# GalvoDAC.net
KiCad netlist of a schematic drawn in Altium Designer
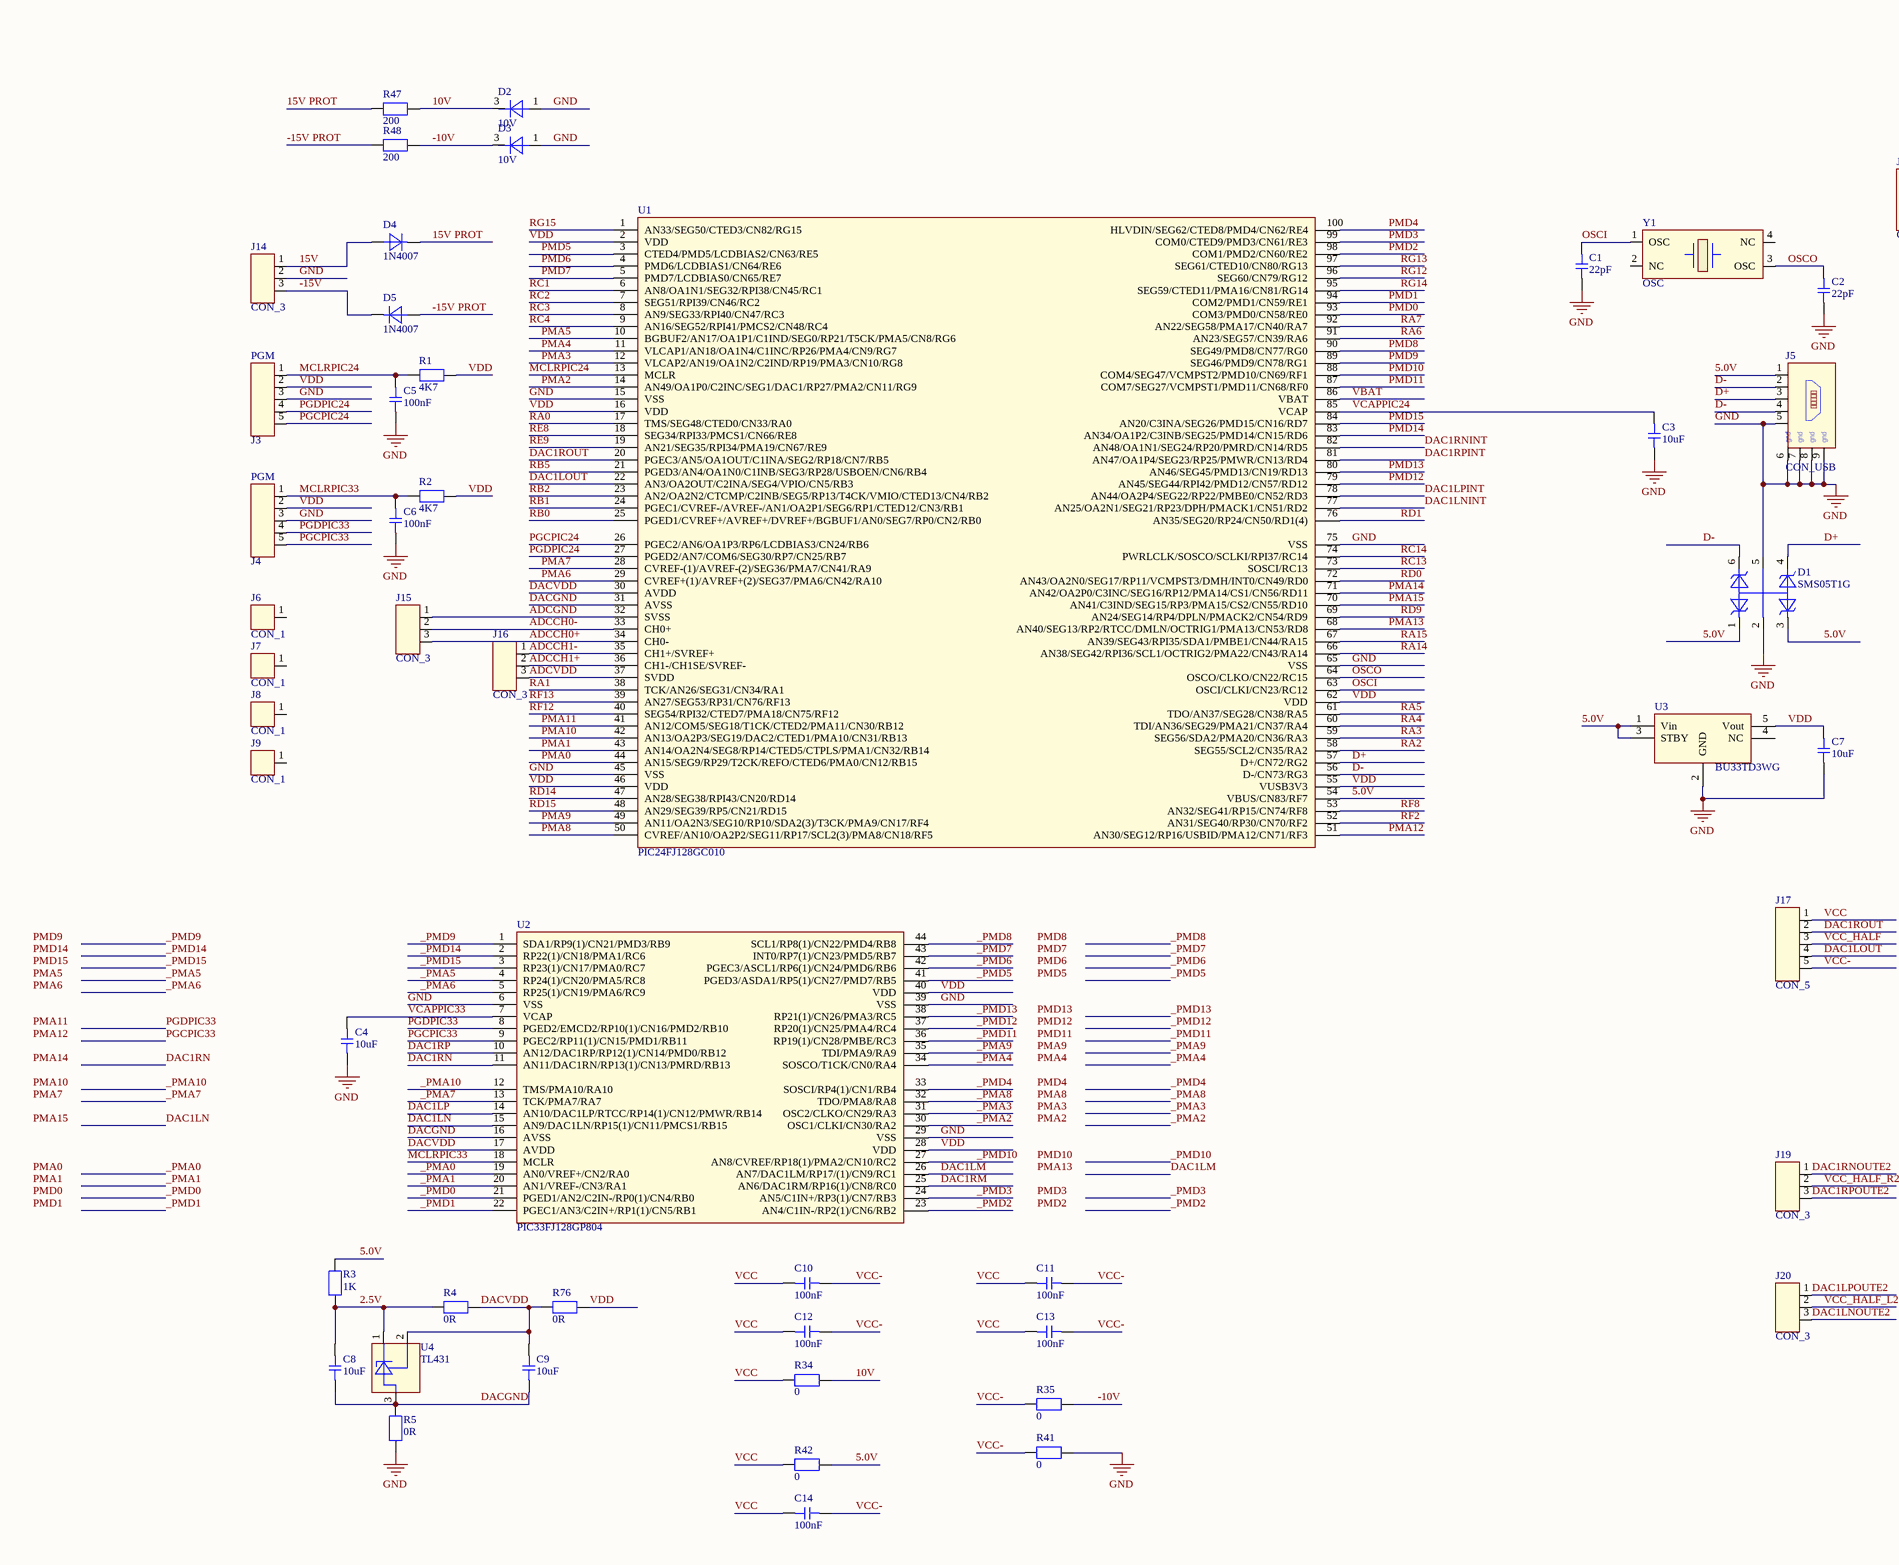
[diagram p0: GalvoDAC.SchDoc, left]
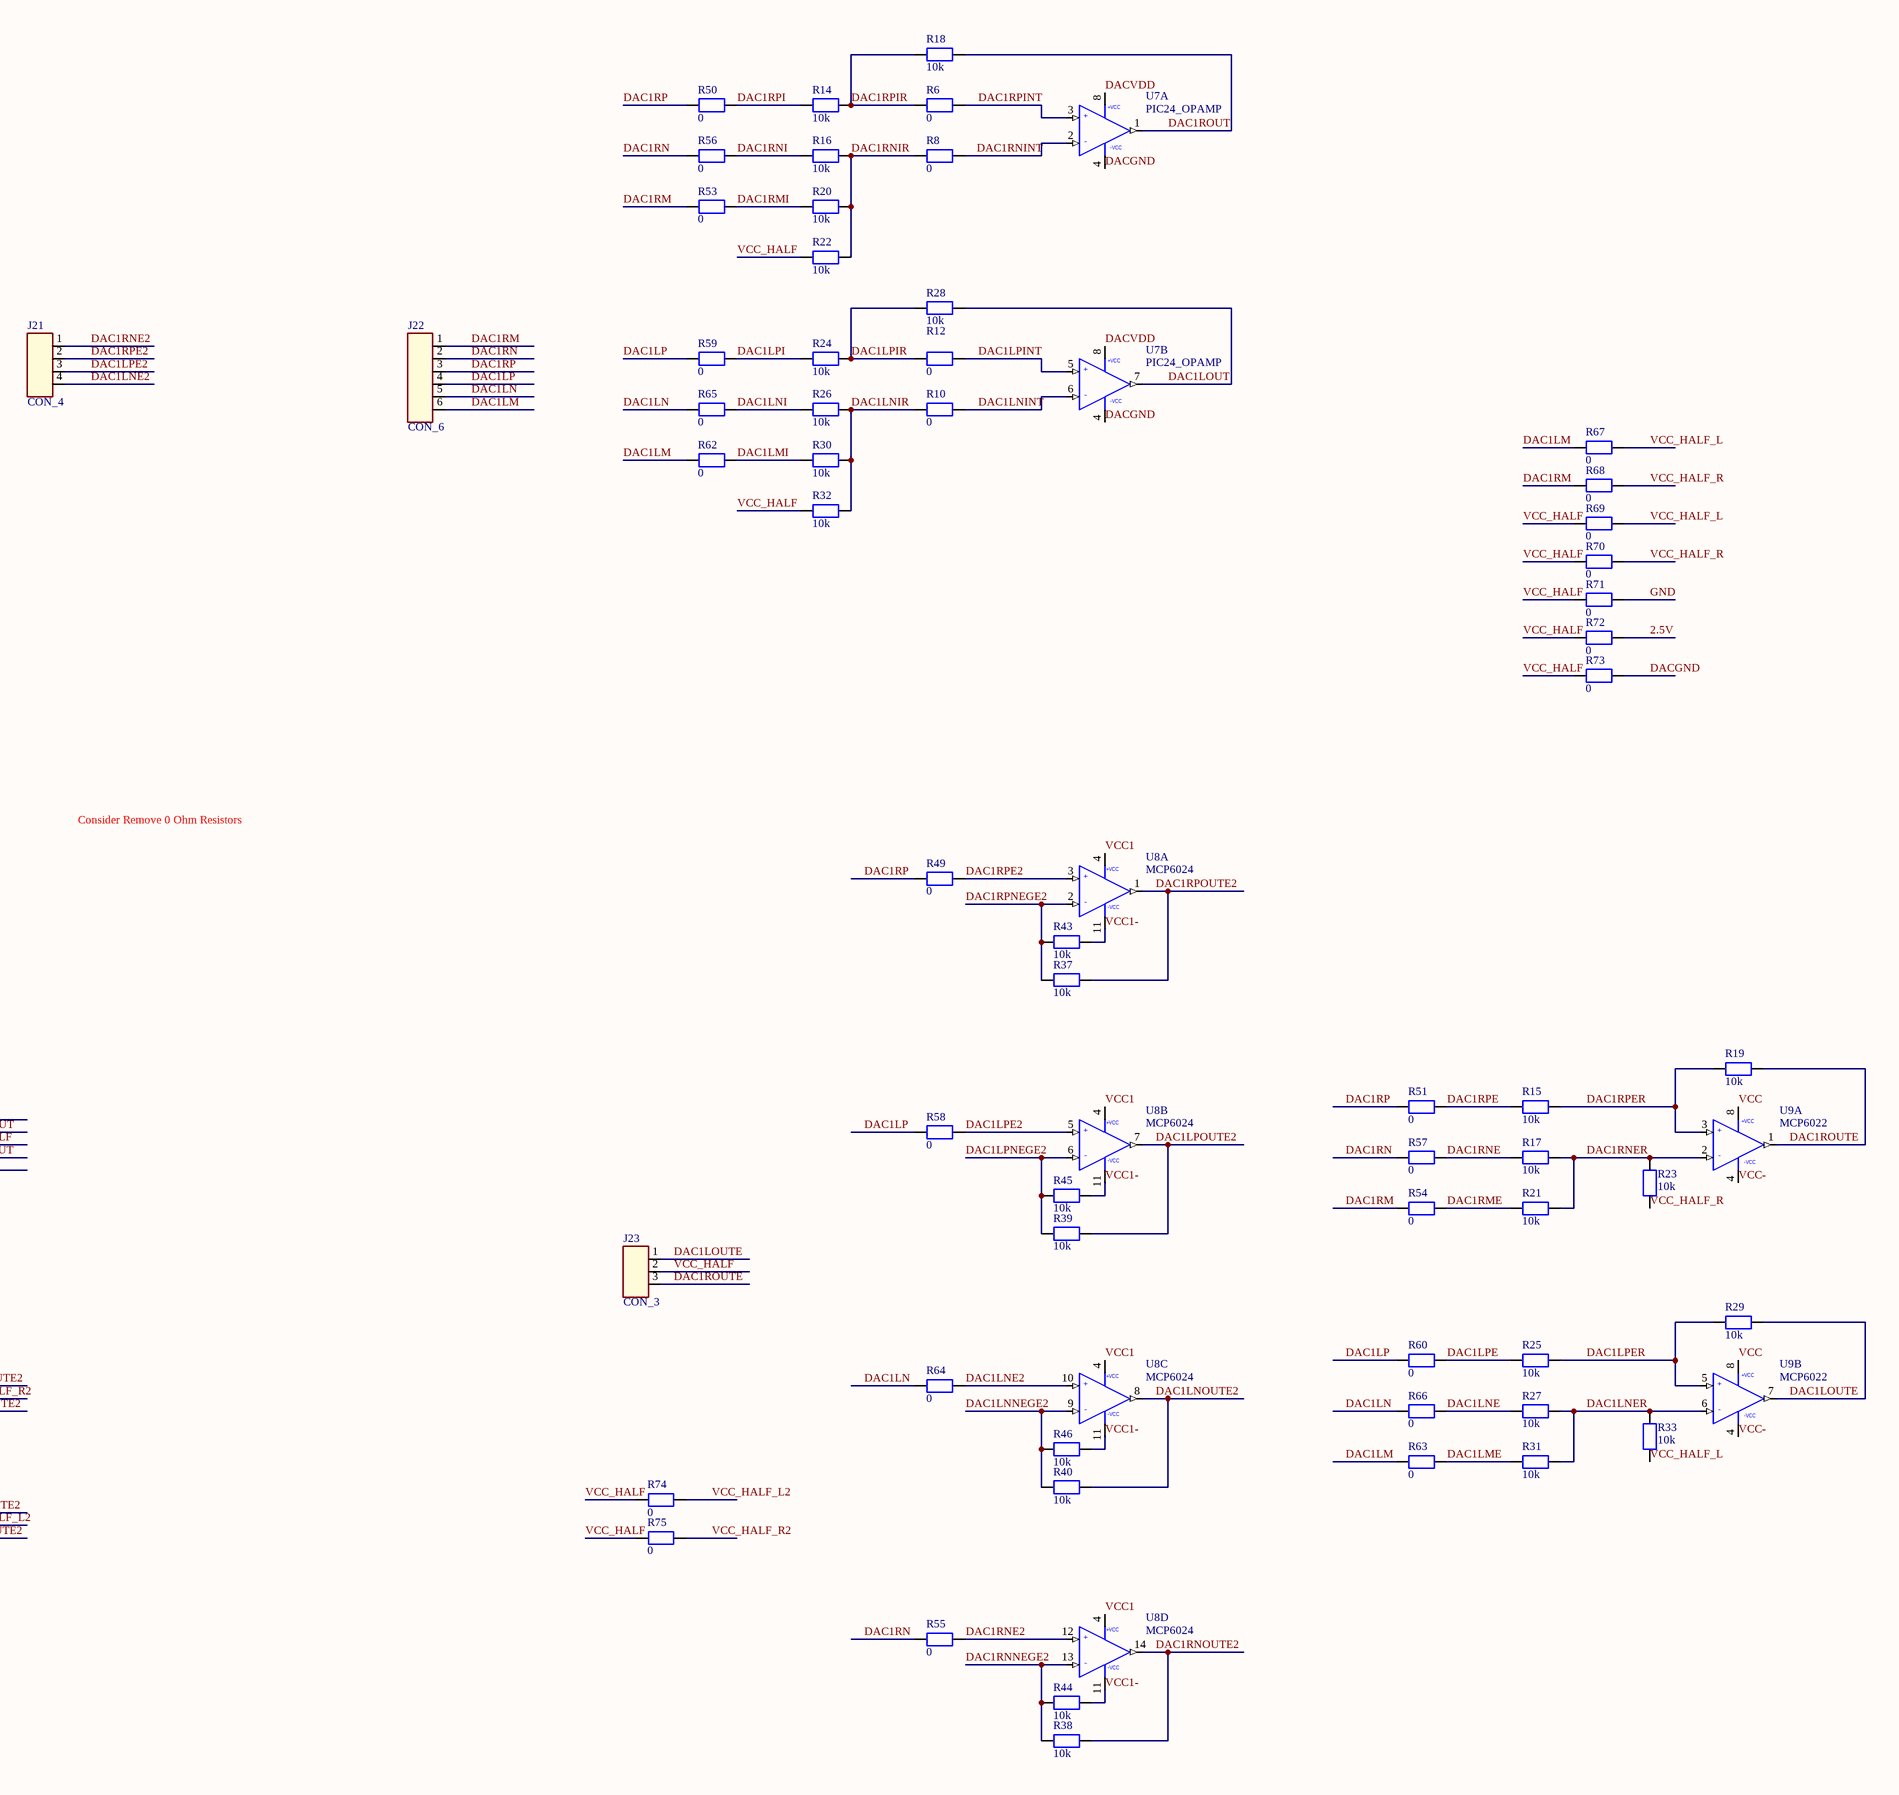
[diagram p1: GalvoDAC.SchDoc, right]

(export (version "E")
  (design (tool "Eeschema 10.0.6"))
  (components
    (comp (ref "C1")
      (value "22pF")
      (footprint "0603_C")
      (description "Capacitor")
      (fields (field (name "Comment") "C") (field (name "PUBLISHER") "Altium Limited"))
      (libsource (lib "HEX") (part "C"))
    )
    (comp (ref "C2")
      (value "22pF")
      (footprint "0603_C")
      (description "Capacitor")
      (fields (field (name "Comment") "C") (field (name "PUBLISHER") "Altium Limited"))
      (libsource (lib "HEX") (part "C"))
    )
    (comp (ref "C3")
      (value "10uF")
      (footprint "0603_C")
      (description "Capacitor")
      (fields (field (name "Comment") "C") (field (name "PUBLISHER") "Altium Limited"))
      (libsource (lib "HEX") (part "C"))
    )
    (comp (ref "C4")
      (value "10uF")
      (footprint "0603_C")
      (description "Capacitor")
      (fields (field (name "Comment") "C") (field (name "PUBLISHER") "Altium Limited"))
      (libsource (lib "HEX") (part "C"))
    )
    (comp (ref "C5")
      (value "100nF")
      (footprint "0603_C")
      (description "Capacitor")
      (fields (field (name "Comment") "C") (field (name "PUBLISHER") "Altium Limited"))
      (libsource (lib "HEX") (part "C"))
    )
    (comp (ref "C6")
      (value "100nF")
      (footprint "0603_C")
      (description "Capacitor")
      (fields (field (name "Comment") "C") (field (name "PUBLISHER") "Altium Limited"))
      (libsource (lib "HEX") (part "C"))
    )
    (comp (ref "C7")
      (value "10uF")
      (footprint "0603_C")
      (description "Capacitor")
      (fields (field (name "Comment") "C") (field (name "PUBLISHER") "Altium Limited"))
      (libsource (lib "HEX") (part "C"))
    )
    (comp (ref "C8")
      (value "10uF")
      (footprint "0603_C")
      (description "Capacitor")
      (fields (field (name "Comment") "C") (field (name "PUBLISHER") "Altium Limited"))
      (libsource (lib "HEX") (part "C"))
    )
    (comp (ref "C9")
      (value "10uF")
      (footprint "0603_C")
      (description "Capacitor")
      (fields (field (name "Comment") "C") (field (name "PUBLISHER") "Altium Limited"))
      (libsource (lib "HEX") (part "C"))
    )
    (comp (ref "C10")
      (value "100nF")
      (footprint "0603_C")
      (description "Capacitor")
      (fields (field (name "Comment") "C") (field (name "PUBLISHER") "Altium Limited"))
      (libsource (lib "HEX") (part "C"))
    )
    (comp (ref "C11")
      (value "100nF")
      (footprint "0603_C")
      (description "Capacitor")
      (fields (field (name "Comment") "C") (field (name "PUBLISHER") "Altium Limited"))
      (libsource (lib "HEX") (part "C"))
    )
    (comp (ref "C12")
      (value "100nF")
      (footprint "0603_C")
      (description "Capacitor")
      (fields (field (name "Comment") "C") (field (name "PUBLISHER") "Altium Limited"))
      (libsource (lib "HEX") (part "C"))
    )
    (comp (ref "C13")
      (value "100nF")
      (footprint "0603_C")
      (description "Capacitor")
      (fields (field (name "Comment") "C") (field (name "PUBLISHER") "Altium Limited"))
      (libsource (lib "HEX") (part "C"))
    )
    (comp (ref "C14")
      (value "100nF")
      (footprint "0603_C")
      (description "Capacitor")
      (fields (field (name "Comment") "C") (field (name "PUBLISHER") "Altium Limited"))
      (libsource (lib "HEX") (part "C"))
    )
    (comp (ref "D1")
      (value "SMS05T1G")
      (footprint "SOT23_6")
      (description "TVS like SMS05T1G")
      (libsource (lib "HEX") (part "D_TVS_QUAD_C1AA2AA5C3C4C6"))
    )
    (comp (ref "D2")
      (value "10V")
      (footprint "SOT23_3")
      (description "Diodes like 1N4148")
      (libsource (lib "HEX") (part "D_A1C3"))
    )
    (comp (ref "D3")
      (value "10V")
      (footprint "SOT23_3")
      (description "Diodes like 1N4148")
      (libsource (lib "HEX") (part "D_A1C3"))
    )
    (comp (ref "D4")
      (value "1N4007")
      (footprint "SMA")
      (description "Diode")
      (libsource (lib "HEX") (part "D"))
    )
    (comp (ref "D5")
      (value "1N4007")
      (footprint "SMA")
      (description "Diode")
      (libsource (lib "HEX") (part "D"))
    )
    (comp (ref "J3")
      (value "PGM")
      (footprint "HDR_254_5")
      (description "Header 5 Pins")
      (fields (field (name "Comment") "CON_5"))
      (libsource (lib "HEX") (part "CON_5"))
    )
    (comp (ref "J4")
      (value "PGM")
      (footprint "HDR_254_5")
      (description "Header 5 Pins")
      (fields (field (name "Comment") "CON_5"))
      (libsource (lib "HEX") (part "CON_5"))
    )
    (comp (ref "J5") (value "CON_USB") (footprint "CON_USB_MINI") (libsource (lib "HEX") (part "CON_USB")))
    (comp (ref "J6")
      (value "CON_1")
      (footprint "MOUNT_HOLE")
      (description "Mounting Hole")
      (libsource (lib "HEX") (part "CON_1"))
    )
    (comp (ref "J7")
      (value "CON_1")
      (footprint "MOUNT_HOLE")
      (description "Mounting Hole")
      (libsource (lib "HEX") (part "CON_1"))
    )
    (comp (ref "J8")
      (value "CON_1")
      (footprint "MOUNT_HOLE")
      (description "Mounting Hole")
      (libsource (lib "HEX") (part "CON_1"))
    )
    (comp (ref "J9")
      (value "CON_1")
      (footprint "MOUNT_HOLE")
      (description "Mounting Hole")
      (libsource (lib "HEX") (part "CON_1"))
    )
    (comp (ref "J14")
      (value "CON_3")
      (footprint "HDR_350_3")
      (description "Header 3 Pins")
      (libsource (lib "HEX") (part "CON_3"))
    )
    (comp (ref "J15")
      (value "CON_3")
      (footprint "HDR_254_3")
      (description "Header 3 Pins")
      (libsource (lib "HEX") (part "CON_3"))
    )
    (comp (ref "J16")
      (value "CON_3")
      (footprint "HDR_254_3")
      (description "Header 3 Pins")
      (libsource (lib "HEX") (part "CON_3"))
    )
    (comp (ref "J17")
      (value "CON_5")
      (footprint "HDR_254_5")
      (description "Header 5 Pins")
      (libsource (lib "HEX") (part "CON_5"))
    )
    (comp (ref "J19")
      (value "CON_3")
      (footprint "HDR_350_3")
      (description "Header 3 Pins")
      (libsource (lib "HEX") (part "CON_3"))
    )
    (comp (ref "J20")
      (value "CON_3")
      (footprint "HDR_350_3")
      (description "Header 3 Pins")
      (libsource (lib "HEX") (part "CON_3"))
    )
    (comp (ref "J21")
      (value "CON_4")
      (footprint "HDR_254_4")
      (description "Header 4 Pins")
      (libsource (lib "HEX") (part "CON_4"))
    )
    (comp (ref "J22")
      (value "CON_6")
      (footprint "HDR_254_6")
      (description "Header 6 Pins")
      (libsource (lib "HEX") (part "CON_6"))
    )
    (comp (ref "J23")
      (value "CON_3")
      (footprint "HDR_350_3")
      (description "Header 3 Pins")
      (libsource (lib "HEX") (part "CON_3"))
    )
    (comp (ref "R1")
      (value "4K7")
      (footprint "0603_R")
      (description "Resistor")
      (fields (field (name "Comment") "R") (field (name "PUBLISHER") "Altium Limited"))
      (libsource (lib "HEX") (part "R"))
    )
    (comp (ref "R2")
      (value "4K7")
      (footprint "0603_R")
      (description "Resistor")
      (fields (field (name "Comment") "R") (field (name "PUBLISHER") "Altium Limited"))
      (libsource (lib "HEX") (part "R"))
    )
    (comp (ref "R3")
      (value "1K")
      (footprint "0603_R")
      (description "Resistor")
      (fields (field (name "Comment") "R") (field (name "PUBLISHER") "Altium Limited"))
      (libsource (lib "HEX") (part "R"))
    )
    (comp (ref "R4")
      (value "0R")
      (footprint "0603_R")
      (description "Resistor")
      (fields (field (name "Comment") "R") (field (name "PUBLISHER") "Altium Limited"))
      (libsource (lib "HEX") (part "R"))
    )
    (comp (ref "R5")
      (value "0R")
      (footprint "0603_R")
      (description "Resistor")
      (fields (field (name "Comment") "R") (field (name "PUBLISHER") "Altium Limited"))
      (libsource (lib "HEX") (part "R"))
    )
    (comp (ref "R6")
      (value "0")
      (footprint "0603_R")
      (description "Resistor")
      (fields (field (name "PUBLISHER") "Altium Limited"))
      (libsource (lib "HEX") (part "R"))
    )
    (comp (ref "R8")
      (value "0")
      (footprint "0603_R")
      (description "Resistor")
      (fields (field (name "PUBLISHER") "Altium Limited"))
      (libsource (lib "HEX") (part "R"))
    )
    (comp (ref "R10")
      (value "0")
      (footprint "0603_R")
      (description "Resistor")
      (fields (field (name "PUBLISHER") "Altium Limited"))
      (libsource (lib "HEX") (part "R"))
    )
    (comp (ref "R12")
      (value "0")
      (footprint "0603_R")
      (description "Resistor")
      (fields (field (name "PUBLISHER") "Altium Limited"))
      (libsource (lib "HEX") (part "R"))
    )
    (comp (ref "R14")
      (value "10k")
      (footprint "0603_R")
      (description "Resistor")
      (fields (field (name "PUBLISHER") "Altium Limited"))
      (libsource (lib "HEX") (part "R"))
    )
    (comp (ref "R15")
      (value "10k")
      (footprint "0603_R")
      (description "Resistor")
      (fields (field (name "PUBLISHER") "Altium Limited"))
      (libsource (lib "HEX") (part "R"))
    )
    (comp (ref "R16")
      (value "10k")
      (footprint "0603_R")
      (description "Resistor")
      (fields (field (name "PUBLISHER") "Altium Limited"))
      (libsource (lib "HEX") (part "R"))
    )
    (comp (ref "R17")
      (value "10k")
      (footprint "0603_R")
      (description "Resistor")
      (fields (field (name "PUBLISHER") "Altium Limited"))
      (libsource (lib "HEX") (part "R"))
    )
    (comp (ref "R18")
      (value "10k")
      (footprint "0603_R")
      (description "Resistor")
      (fields (field (name "PUBLISHER") "Altium Limited"))
      (libsource (lib "HEX") (part "R"))
    )
    (comp (ref "R19")
      (value "10k")
      (footprint "0603_R")
      (description "Resistor")
      (fields (field (name "PUBLISHER") "Altium Limited"))
      (libsource (lib "HEX") (part "R"))
    )
    (comp (ref "R20")
      (value "10k")
      (footprint "0603_R")
      (description "Resistor")
      (fields (field (name "PUBLISHER") "Altium Limited"))
      (libsource (lib "HEX") (part "R"))
    )
    (comp (ref "R21")
      (value "10k")
      (footprint "0603_R")
      (description "Resistor")
      (fields (field (name "PUBLISHER") "Altium Limited"))
      (libsource (lib "HEX") (part "R"))
    )
    (comp (ref "R22")
      (value "10k")
      (footprint "0603_R")
      (description "Resistor")
      (fields (field (name "PUBLISHER") "Altium Limited"))
      (libsource (lib "HEX") (part "R"))
    )
    (comp (ref "R23")
      (value "10k")
      (footprint "0603_R")
      (description "Resistor")
      (fields (field (name "PUBLISHER") "Altium Limited"))
      (libsource (lib "HEX") (part "R"))
    )
    (comp (ref "R24")
      (value "10k")
      (footprint "0603_R")
      (description "Resistor")
      (fields (field (name "PUBLISHER") "Altium Limited"))
      (libsource (lib "HEX") (part "R"))
    )
    (comp (ref "R25")
      (value "10k")
      (footprint "0603_R")
      (description "Resistor")
      (fields (field (name "PUBLISHER") "Altium Limited"))
      (libsource (lib "HEX") (part "R"))
    )
    (comp (ref "R26")
      (value "10k")
      (footprint "0603_R")
      (description "Resistor")
      (fields (field (name "PUBLISHER") "Altium Limited"))
      (libsource (lib "HEX") (part "R"))
    )
    (comp (ref "R27")
      (value "10k")
      (footprint "0603_R")
      (description "Resistor")
      (fields (field (name "PUBLISHER") "Altium Limited"))
      (libsource (lib "HEX") (part "R"))
    )
    (comp (ref "R28")
      (value "10k")
      (footprint "0603_R")
      (description "Resistor")
      (fields (field (name "PUBLISHER") "Altium Limited"))
      (libsource (lib "HEX") (part "R"))
    )
    (comp (ref "R29")
      (value "10k")
      (footprint "0603_R")
      (description "Resistor")
      (fields (field (name "PUBLISHER") "Altium Limited"))
      (libsource (lib "HEX") (part "R"))
    )
    (comp (ref "R30")
      (value "10k")
      (footprint "0603_R")
      (description "Resistor")
      (fields (field (name "PUBLISHER") "Altium Limited"))
      (libsource (lib "HEX") (part "R"))
    )
    (comp (ref "R31")
      (value "10k")
      (footprint "0603_R")
      (description "Resistor")
      (fields (field (name "PUBLISHER") "Altium Limited"))
      (libsource (lib "HEX") (part "R"))
    )
    (comp (ref "R32")
      (value "10k")
      (footprint "0603_R")
      (description "Resistor")
      (fields (field (name "PUBLISHER") "Altium Limited"))
      (libsource (lib "HEX") (part "R"))
    )
    (comp (ref "R33")
      (value "10k")
      (footprint "0603_R")
      (description "Resistor")
      (fields (field (name "PUBLISHER") "Altium Limited"))
      (libsource (lib "HEX") (part "R"))
    )
    (comp (ref "R34")
      (value "0")
      (footprint "0603_R")
      (description "Resistor")
      (fields (field (name "PUBLISHER") "Altium Limited"))
      (libsource (lib "HEX") (part "R"))
    )
    (comp (ref "R35")
      (value "0")
      (footprint "0603_R")
      (description "Resistor")
      (fields (field (name "PUBLISHER") "Altium Limited"))
      (libsource (lib "HEX") (part "R"))
    )
    (comp (ref "R37")
      (value "10k")
      (footprint "0603_R")
      (description "Resistor")
      (fields (field (name "PUBLISHER") "Altium Limited"))
      (libsource (lib "HEX") (part "R"))
    )
    (comp (ref "R38")
      (value "10k")
      (footprint "0603_R")
      (description "Resistor")
      (fields (field (name "PUBLISHER") "Altium Limited"))
      (libsource (lib "HEX") (part "R"))
    )
    (comp (ref "R39")
      (value "10k")
      (footprint "0603_R")
      (description "Resistor")
      (fields (field (name "PUBLISHER") "Altium Limited"))
      (libsource (lib "HEX") (part "R"))
    )
    (comp (ref "R40")
      (value "10k")
      (footprint "0603_R")
      (description "Resistor")
      (fields (field (name "PUBLISHER") "Altium Limited"))
      (libsource (lib "HEX") (part "R"))
    )
    (comp (ref "R41")
      (value "0")
      (footprint "0603_R")
      (description "Resistor")
      (fields (field (name "PUBLISHER") "Altium Limited"))
      (libsource (lib "HEX") (part "R"))
    )
    (comp (ref "R42")
      (value "0")
      (footprint "0603_R")
      (description "Resistor")
      (fields (field (name "PUBLISHER") "Altium Limited"))
      (libsource (lib "HEX") (part "R"))
    )
    (comp (ref "R43")
      (value "10k")
      (footprint "0603_R")
      (description "Resistor")
      (fields (field (name "PUBLISHER") "Altium Limited"))
      (libsource (lib "HEX") (part "R"))
    )
    (comp (ref "R44")
      (value "10k")
      (footprint "0603_R")
      (description "Resistor")
      (fields (field (name "PUBLISHER") "Altium Limited"))
      (libsource (lib "HEX") (part "R"))
    )
    (comp (ref "R45")
      (value "10k")
      (footprint "0603_R")
      (description "Resistor")
      (fields (field (name "PUBLISHER") "Altium Limited"))
      (libsource (lib "HEX") (part "R"))
    )
    (comp (ref "R46")
      (value "10k")
      (footprint "0603_R")
      (description "Resistor")
      (fields (field (name "PUBLISHER") "Altium Limited"))
      (libsource (lib "HEX") (part "R"))
    )
    (comp (ref "R47")
      (value "200")
      (footprint "0603_R")
      (description "Resistor")
      (fields (field (name "Comment") "R") (field (name "PUBLISHER") "Altium Limited"))
      (libsource (lib "HEX") (part "R"))
    )
    (comp (ref "R48")
      (value "200")
      (footprint "0603_R")
      (description "Resistor")
      (fields (field (name "Comment") "R") (field (name "PUBLISHER") "Altium Limited"))
      (libsource (lib "HEX") (part "R"))
    )
    (comp (ref "R49")
      (value "0")
      (footprint "0603_R")
      (description "Resistor")
      (fields (field (name "PUBLISHER") "Altium Limited"))
      (libsource (lib "HEX") (part "R"))
    )
    (comp (ref "R50")
      (value "0")
      (footprint "0603_R")
      (description "Resistor")
      (fields (field (name "PUBLISHER") "Altium Limited"))
      (libsource (lib "HEX") (part "R"))
    )
    (comp (ref "R51")
      (value "0")
      (footprint "0603_R")
      (description "Resistor")
      (fields (field (name "PUBLISHER") "Altium Limited"))
      (libsource (lib "HEX") (part "R"))
    )
    (comp (ref "R53")
      (value "0")
      (footprint "0603_R")
      (description "Resistor")
      (fields (field (name "PUBLISHER") "Altium Limited"))
      (libsource (lib "HEX") (part "R"))
    )
    (comp (ref "R54")
      (value "0")
      (footprint "0603_R")
      (description "Resistor")
      (fields (field (name "PUBLISHER") "Altium Limited"))
      (libsource (lib "HEX") (part "R"))
    )
    (comp (ref "R55")
      (value "0")
      (footprint "0603_R")
      (description "Resistor")
      (fields (field (name "PUBLISHER") "Altium Limited"))
      (libsource (lib "HEX") (part "R"))
    )
    (comp (ref "R56")
      (value "0")
      (footprint "0603_R")
      (description "Resistor")
      (fields (field (name "PUBLISHER") "Altium Limited"))
      (libsource (lib "HEX") (part "R"))
    )
    (comp (ref "R57")
      (value "0")
      (footprint "0603_R")
      (description "Resistor")
      (fields (field (name "PUBLISHER") "Altium Limited"))
      (libsource (lib "HEX") (part "R"))
    )
    (comp (ref "R58")
      (value "0")
      (footprint "0603_R")
      (description "Resistor")
      (fields (field (name "PUBLISHER") "Altium Limited"))
      (libsource (lib "HEX") (part "R"))
    )
    (comp (ref "R59")
      (value "0")
      (footprint "0603_R")
      (description "Resistor")
      (fields (field (name "PUBLISHER") "Altium Limited"))
      (libsource (lib "HEX") (part "R"))
    )
    (comp (ref "R60")
      (value "0")
      (footprint "0603_R")
      (description "Resistor")
      (fields (field (name "PUBLISHER") "Altium Limited"))
      (libsource (lib "HEX") (part "R"))
    )
    (comp (ref "R62")
      (value "0")
      (footprint "0603_R")
      (description "Resistor")
      (fields (field (name "PUBLISHER") "Altium Limited"))
      (libsource (lib "HEX") (part "R"))
    )
    (comp (ref "R63")
      (value "0")
      (footprint "0603_R")
      (description "Resistor")
      (fields (field (name "PUBLISHER") "Altium Limited"))
      (libsource (lib "HEX") (part "R"))
    )
    (comp (ref "R64")
      (value "0")
      (footprint "0603_R")
      (description "Resistor")
      (fields (field (name "PUBLISHER") "Altium Limited"))
      (libsource (lib "HEX") (part "R"))
    )
    (comp (ref "R65")
      (value "0")
      (footprint "0603_R")
      (description "Resistor")
      (fields (field (name "PUBLISHER") "Altium Limited"))
      (libsource (lib "HEX") (part "R"))
    )
    (comp (ref "R66")
      (value "0")
      (footprint "0603_R")
      (description "Resistor")
      (fields (field (name "PUBLISHER") "Altium Limited"))
      (libsource (lib "HEX") (part "R"))
    )
    (comp (ref "R67")
      (value "0")
      (footprint "0603_R")
      (description "Resistor")
      (fields (field (name "PUBLISHER") "Altium Limited"))
      (libsource (lib "HEX") (part "R"))
    )
    (comp (ref "R68")
      (value "0")
      (footprint "0603_R")
      (description "Resistor")
      (fields (field (name "PUBLISHER") "Altium Limited"))
      (libsource (lib "HEX") (part "R"))
    )
    (comp (ref "R69")
      (value "0")
      (footprint "0603_R")
      (description "Resistor")
      (fields (field (name "PUBLISHER") "Altium Limited"))
      (libsource (lib "HEX") (part "R"))
    )
    (comp (ref "R70")
      (value "0")
      (footprint "0603_R")
      (description "Resistor")
      (fields (field (name "PUBLISHER") "Altium Limited"))
      (libsource (lib "HEX") (part "R"))
    )
    (comp (ref "R71")
      (value "0")
      (footprint "0603_R")
      (description "Resistor")
      (fields (field (name "PUBLISHER") "Altium Limited"))
      (libsource (lib "HEX") (part "R"))
    )
    (comp (ref "R72")
      (value "0")
      (footprint "0603_R")
      (description "Resistor")
      (fields (field (name "PUBLISHER") "Altium Limited"))
      (libsource (lib "HEX") (part "R"))
    )
    (comp (ref "R73")
      (value "0")
      (footprint "0603_R")
      (description "Resistor")
      (fields (field (name "PUBLISHER") "Altium Limited"))
      (libsource (lib "HEX") (part "R"))
    )
    (comp (ref "R74")
      (value "0")
      (footprint "0603_R")
      (description "Resistor")
      (fields (field (name "PUBLISHER") "Altium Limited"))
      (libsource (lib "HEX") (part "R"))
    )
    (comp (ref "R75")
      (value "0")
      (footprint "0603_R")
      (description "Resistor")
      (fields (field (name "PUBLISHER") "Altium Limited"))
      (libsource (lib "HEX") (part "R"))
    )
    (comp (ref "R76")
      (value "0R")
      (footprint "0603_R")
      (description "Resistor")
      (fields (field (name "Comment") "R") (field (name "PUBLISHER") "Altium Limited"))
      (libsource (lib "HEX") (part "R"))
    )
    (comp (ref "U1")
      (value "PIC24FJ128GC010")
      (footprint "TQFP_100")
      (fields (field (name "Comment") "IC_PIC24FJ128GC010"))
      (libsource (lib "HEX") (part "IC_PIC24FJ128GC010"))
    )
    (comp (ref "U2")
      (value "PIC33FJ128GP804")
      (footprint "TQFP_44")
      (fields (field (name "Comment") "IC_PIC33FJ128GP804"))
      (libsource (lib "HEX") (part "IC_PIC33FJ128GP804"))
    )
    (comp (ref "U3")
      (value "BU33TD3WG")
      (footprint "SOT23_5")
      (description "LDO 5 to 3.3V")
      (libsource (lib "HEX") (part "IC_BU33TD3WG"))
    )
    (comp (ref "U4")
      (value "TL431")
      (footprint "SOT23_3")
      (fields (field (name "Comment") "IC_TL431_SOT23_3"))
      (libsource (lib "HEX") (part "IC_TL431_SOT23_3"))
    )
    (comp (ref "U7")
      (value "PIC24_OPAMP")
      (description "Opamp x 2")
      (libsource (lib "HEX") (part "IC_MCP6022"))
    )
    (comp (ref "U8")
      (value "MCP6024")
      (footprint "SOIC_14")
      (description "Opamp x 4")
      (libsource (lib "HEX") (part "IC_MCP6024"))
    )
    (comp (ref "U9")
      (value "MCP6022")
      (footprint "SOIC_8")
      (description "Opamp x 2")
      (libsource (lib "HEX") (part "IC_MCP6022"))
    )
    (comp (ref "Y1")
      (value "OSC")
      (footprint "OSC_DFN_2x2.5mm")
      (fields (field (name "Comment") "XTAL_OSC1OSC3"))
      (libsource (lib "HEX") (part "XTAL_OSC1OSC3"))
    )
  )
  (nets
    (net (code "1") (name "/-10V") (class "Default")
      (node (ref "D3") (pin "3") (pinfunction "C_3") (pintype "passive"))
      (node (ref "R35") (pin "2") (pinfunction "2_2") (pintype "passive"))
      (node (ref "R48") (pin "2") (pinfunction "2_2") (pintype "passive"))
    )
    (net (code "2") (name "/-15V") (class "Default")
      (node (ref "D5") (pin "1") (pinfunction "C_1") (pintype "passive"))
      (node (ref "J14") (pin "3") (pinfunction "3_3") (pintype "passive"))
    )
    (net (code "3") (name "/-15V PROT") (class "Default")
      (node (ref "D5") (pin "2") (pinfunction "A_2") (pintype "passive"))
      (node (ref "R48") (pin "1") (pinfunction "1_1") (pintype "passive"))
    )
    (net (code "4") (name "/2.5V") (class "Default")
      (node (ref "C8") (pin "2") (pinfunction "2_2") (pintype "passive"))
      (node (ref "R3") (pin "1") (pinfunction "1_1") (pintype "passive"))
      (node (ref "R4") (pin "1") (pinfunction "1_1") (pintype "passive"))
      (node (ref "R72") (pin "2") (pinfunction "2_2") (pintype "passive"))
      (node (ref "U4") (pin "1") (pinfunction "Cathode_1") (pintype "passive"))
    )
    (net (code "5") (name "/5.0V") (class "Default")
      (node (ref "D1") (pin "1") (pinfunction "C1_1") (pintype "passive"))
      (node (ref "D1") (pin "3") (pinfunction "C2_3") (pintype "passive"))
      (node (ref "J5") (pin "1") (pinfunction "1_1") (pintype "passive"))
      (node (ref "R3") (pin "2") (pinfunction "2_2") (pintype "passive"))
      (node (ref "R42") (pin "2") (pinfunction "2_2") (pintype "passive"))
      (node (ref "U1") (pin "54") (pinfunction "VBUS/CN83/RF7_54") (pintype "passive"))
      (node (ref "U3") (pin "1") (pinfunction "Vin_1") (pintype "passive"))
      (node (ref "U3") (pin "3") (pinfunction "STBY_3") (pintype "passive"))
    )
    (net (code "6") (name "/10V") (class "Default")
      (node (ref "D2") (pin "3") (pinfunction "C_3") (pintype "passive"))
      (node (ref "R34") (pin "2") (pinfunction "2_2") (pintype "passive"))
      (node (ref "R47") (pin "2") (pinfunction "2_2") (pintype "passive"))
    )
    (net (code "7") (name "/15V") (class "Default")
      (node (ref "D4") (pin "2") (pinfunction "A_2") (pintype "passive"))
      (node (ref "J14") (pin "1") (pinfunction "1_1") (pintype "passive"))
    )
    (net (code "8") (name "/15V PROT") (class "Default")
      (node (ref "D4") (pin "1") (pinfunction "C_1") (pintype "passive"))
      (node (ref "R47") (pin "1") (pinfunction "1_1") (pintype "passive"))
    )
    (net (code "9") (name "/ADCCH0+") (class "Default")
      (node (ref "J15") (pin "3") (pinfunction "3_3") (pintype "passive"))
      (node (ref "U1") (pin "34") (pinfunction "CH0-_34") (pintype "passive"))
    )
    (net (code "10") (name "/ADCCH0-") (class "Default")
      (node (ref "J15") (pin "2") (pinfunction "2_2") (pintype "passive"))
      (node (ref "U1") (pin "33") (pinfunction "CH0+_33") (pintype "passive"))
    )
    (net (code "11") (name "/ADCCH1+") (class "Default")
      (node (ref "J16") (pin "2") (pinfunction "2_2") (pintype "passive"))
      (node (ref "U1") (pin "36") (pinfunction "CH1-/CH1SE/SVREF-_36") (pintype "passive"))
    )
    (net (code "12") (name "/ADCCH1-") (class "Default")
      (node (ref "J16") (pin "1") (pinfunction "1_1") (pintype "passive"))
      (node (ref "U1") (pin "35") (pinfunction "CH1+/SVREF+_35") (pintype "passive"))
    )
    (net (code "13") (name "/ADCGND") (class "Default")
      (node (ref "J15") (pin "1") (pinfunction "1_1") (pintype "passive"))
      (node (ref "U1") (pin "32") (pinfunction "SVSS_32") (pintype "passive"))
    )
    (net (code "14") (name "/ADCVDD") (class "Default")
      (node (ref "J16") (pin "3") (pinfunction "3_3") (pintype "passive"))
      (node (ref "U1") (pin "37") (pinfunction "SVDD_37") (pintype "passive"))
    )
    (net (code "15") (name "/D+") (class "Default")
      (node (ref "D1") (pin "4") (pinfunction "C3_4") (pintype "passive"))
      (node (ref "J5") (pin "3") (pinfunction "3_3") (pintype "passive"))
      (node (ref "U1") (pin "57") (pinfunction "D+/CN72/RG2_57") (pintype "passive"))
    )
    (net (code "16") (name "/D-") (class "Default")
      (node (ref "D1") (pin "6") (pinfunction "C4_6") (pintype "passive"))
      (node (ref "J5") (pin "2") (pinfunction "2_2") (pintype "passive"))
      (node (ref "J5") (pin "4") (pinfunction "4_4") (pintype "passive"))
      (node (ref "U1") (pin "56") (pinfunction "D-/CN73/RG3_56") (pintype "passive"))
    )
    (net (code "17") (name "/DAC1LM") (class "Default")
      (node (ref "J22") (pin "6") (pinfunction "6_6") (pintype "passive"))
      (node (ref "R62") (pin "2") (pinfunction "2_2") (pintype "passive"))
      (node (ref "R63") (pin "2") (pinfunction "2_2") (pintype "passive"))
      (node (ref "R67") (pin "1") (pinfunction "1_1") (pintype "passive"))
      (node (ref "U2") (pin "26") (pinfunction "AN7/DAC1LM/RP17/(1)/CN9/RC1_26") (pintype "passive"))
    )
    (net (code "18") (name "/DAC1LME") (class "Default")
      (node (ref "R31") (pin "2") (pinfunction "2_2") (pintype "passive"))
      (node (ref "R63") (pin "1") (pinfunction "1_1") (pintype "passive"))
    )
    (net (code "19") (name "/DAC1LMI") (class "Default")
      (node (ref "R30") (pin "2") (pinfunction "2_2") (pintype "passive"))
      (node (ref "R62") (pin "1") (pinfunction "1_1") (pintype "passive"))
    )
    (net (code "20") (name "/DAC1LN") (class "Default")
      (node (ref "J22") (pin "5") (pinfunction "5_5") (pintype "passive"))
      (node (ref "R64") (pin "2") (pinfunction "2_2") (pintype "passive"))
      (node (ref "R65") (pin "2") (pinfunction "2_2") (pintype "passive"))
      (node (ref "R66") (pin "2") (pinfunction "2_2") (pintype "passive"))
      (node (ref "U2") (pin "15") (pinfunction "AN9/DAC1LN/RP15(1)/CN11/PMCS1/RB15_15") (pintype "passive"))
    )
    (net (code "21") (name "/DAC1LNE") (class "Default")
      (node (ref "R27") (pin "1") (pinfunction "1_1") (pintype "passive"))
      (node (ref "R66") (pin "1") (pinfunction "1_1") (pintype "passive"))
    )
    (net (code "22") (name "/DAC1LNE2") (class "Default")
      (node (ref "J21") (pin "4") (pinfunction "4_4") (pintype "passive"))
      (node (ref "R64") (pin "1") (pinfunction "1_1") (pintype "passive"))
      (node (ref "U8") (pin "10") (pinfunction "+IN_10") (pintype "input"))
    )
    (net (code "23") (name "/DAC1LNER") (class "Default")
      (node (ref "R27") (pin "2") (pinfunction "2_2") (pintype "passive"))
      (node (ref "R31") (pin "1") (pinfunction "1_1") (pintype "passive"))
      (node (ref "R33") (pin "1") (pinfunction "1_1") (pintype "passive"))
      (node (ref "U9") (pin "6") (pinfunction "-IN_6") (pintype "input"))
    )
    (net (code "24") (name "/DAC1LNI") (class "Default")
      (node (ref "R26") (pin "1") (pinfunction "1_1") (pintype "passive"))
      (node (ref "R65") (pin "1") (pinfunction "1_1") (pintype "passive"))
    )
    (net (code "25") (name "/DAC1LNINT") (class "Default")
      (node (ref "R10") (pin "1") (pinfunction "1_1") (pintype "passive"))
      (node (ref "U1") (pin "77") (pinfunction "AN25/OA2N1/SEG21/RP23/DPH/PMACK1/CN51/RD2_77") (pintype "passive"))
      (node (ref "U7") (pin "6") (pinfunction "-IN_6") (pintype "input"))
    )
    (net (code "26") (name "/DAC1LNIR") (class "Default")
      (node (ref "R10") (pin "2") (pinfunction "2_2") (pintype "passive"))
      (node (ref "R26") (pin "2") (pinfunction "2_2") (pintype "passive"))
      (node (ref "R30") (pin "1") (pinfunction "1_1") (pintype "passive"))
      (node (ref "R32") (pin "1") (pinfunction "1_1") (pintype "passive"))
    )
    (net (code "27") (name "/DAC1LNNEGE2") (class "Default")
      (node (ref "R40") (pin "2") (pinfunction "2_2") (pintype "passive"))
      (node (ref "R46") (pin "2") (pinfunction "2_2") (pintype "passive"))
      (node (ref "U8") (pin "9") (pinfunction "-IN_9") (pintype "input"))
    )
    (net (code "28") (name "/DAC1LNOUTE2") (class "Default")
      (node (ref "J20") (pin "3") (pinfunction "3_3") (pintype "passive"))
      (node (ref "R40") (pin "1") (pinfunction "1_1") (pintype "passive"))
      (node (ref "U8") (pin "8") (pinfunction "OUT_8") (pintype "output"))
    )
    (net (code "29") (name "/DAC1LOUT") (class "Default")
      (node (ref "J17") (pin "4") (pinfunction "4_4") (pintype "passive"))
      (node (ref "R28") (pin "2") (pinfunction "2_2") (pintype "passive"))
      (node (ref "U1") (pin "22") (pinfunction "AN3/OA2OUT/C2INA/SEG4/VPIO/CN5/RB3_22") (pintype "passive"))
      (node (ref "U7") (pin "7") (pinfunction "OUT_7") (pintype "output"))
    )
    (net (code "30") (name "/DAC1LOUTE") (class "Default")
      (node (ref "J23") (pin "1") (pinfunction "1_1") (pintype "passive"))
      (node (ref "R29") (pin "2") (pinfunction "2_2") (pintype "passive"))
      (node (ref "U9") (pin "7") (pinfunction "OUT_7") (pintype "output"))
    )
    (net (code "31") (name "/DAC1LP") (class "Default")
      (node (ref "J22") (pin "4") (pinfunction "4_4") (pintype "passive"))
      (node (ref "R58") (pin "2") (pinfunction "2_2") (pintype "passive"))
      (node (ref "R59") (pin "2") (pinfunction "2_2") (pintype "passive"))
      (node (ref "R60") (pin "2") (pinfunction "2_2") (pintype "passive"))
      (node (ref "U2") (pin "14") (pinfunction "AN10/DAC1LP/RTCC/RP14(1)/CN12/PMWR/RB14_14") (pintype "passive"))
    )
    (net (code "32") (name "/DAC1LPE") (class "Default")
      (node (ref "R25") (pin "1") (pinfunction "1_1") (pintype "passive"))
      (node (ref "R60") (pin "1") (pinfunction "1_1") (pintype "passive"))
    )
    (net (code "33") (name "/DAC1LPE2") (class "Default")
      (node (ref "J21") (pin "3") (pinfunction "3_3") (pintype "passive"))
      (node (ref "R58") (pin "1") (pinfunction "1_1") (pintype "passive"))
      (node (ref "U8") (pin "5") (pinfunction "+IN_5") (pintype "input"))
    )
    (net (code "34") (name "/DAC1LPER") (class "Default")
      (node (ref "R25") (pin "2") (pinfunction "2_2") (pintype "passive"))
      (node (ref "R29") (pin "1") (pinfunction "1_1") (pintype "passive"))
      (node (ref "U9") (pin "5") (pinfunction "+IN_5") (pintype "input"))
    )
    (net (code "35") (name "/DAC1LPI") (class "Default")
      (node (ref "R24") (pin "1") (pinfunction "1_1") (pintype "passive"))
      (node (ref "R59") (pin "1") (pinfunction "1_1") (pintype "passive"))
    )
    (net (code "36") (name "/DAC1LPINT") (class "Default")
      (node (ref "R12") (pin "1") (pinfunction "1_1") (pintype "passive"))
      (node (ref "U1") (pin "78") (pinfunction "AN44/OA2P4/SEG22/RP22/PMBE0/CN52/RD3_78") (pintype "passive"))
      (node (ref "U7") (pin "5") (pinfunction "+IN_5") (pintype "input"))
    )
    (net (code "37") (name "/DAC1LPIR") (class "Default")
      (node (ref "R12") (pin "2") (pinfunction "2_2") (pintype "passive"))
      (node (ref "R24") (pin "2") (pinfunction "2_2") (pintype "passive"))
      (node (ref "R28") (pin "1") (pinfunction "1_1") (pintype "passive"))
    )
    (net (code "38") (name "/DAC1LPNEGE2") (class "Default")
      (node (ref "R39") (pin "2") (pinfunction "2_2") (pintype "passive"))
      (node (ref "R45") (pin "2") (pinfunction "2_2") (pintype "passive"))
      (node (ref "U8") (pin "6") (pinfunction "-IN_6") (pintype "input"))
    )
    (net (code "39") (name "/DAC1LPOUTE2") (class "Default")
      (node (ref "J20") (pin "1") (pinfunction "1_1") (pintype "passive"))
      (node (ref "R39") (pin "1") (pinfunction "1_1") (pintype "passive"))
      (node (ref "U8") (pin "7") (pinfunction "OUT_7") (pintype "output"))
    )
    (net (code "40") (name "/DAC1RM") (class "Default")
      (node (ref "J22") (pin "1") (pinfunction "1_1") (pintype "passive"))
      (node (ref "R53") (pin "2") (pinfunction "2_2") (pintype "passive"))
      (node (ref "R54") (pin "2") (pinfunction "2_2") (pintype "passive"))
      (node (ref "R68") (pin "1") (pinfunction "1_1") (pintype "passive"))
      (node (ref "U2") (pin "25") (pinfunction "AN6/DAC1RM/RP16(1)/CN8/RC0_25") (pintype "passive"))
    )
    (net (code "41") (name "/DAC1RME") (class "Default")
      (node (ref "R21") (pin "2") (pinfunction "2_2") (pintype "passive"))
      (node (ref "R54") (pin "1") (pinfunction "1_1") (pintype "passive"))
    )
    (net (code "42") (name "/DAC1RMI") (class "Default")
      (node (ref "R20") (pin "2") (pinfunction "2_2") (pintype "passive"))
      (node (ref "R53") (pin "1") (pinfunction "1_1") (pintype "passive"))
    )
    (net (code "43") (name "/DAC1RN") (class "Default")
      (node (ref "J22") (pin "2") (pinfunction "2_2") (pintype "passive"))
      (node (ref "R55") (pin "2") (pinfunction "2_2") (pintype "passive"))
      (node (ref "R56") (pin "2") (pinfunction "2_2") (pintype "passive"))
      (node (ref "R57") (pin "2") (pinfunction "2_2") (pintype "passive"))
      (node (ref "U2") (pin "11") (pinfunction "AN11/DAC1RN/RP13(1)/CN13/PMRD/RB13_11") (pintype "passive"))
    )
    (net (code "44") (name "/DAC1RNE") (class "Default")
      (node (ref "R17") (pin "1") (pinfunction "1_1") (pintype "passive"))
      (node (ref "R57") (pin "1") (pinfunction "1_1") (pintype "passive"))
    )
    (net (code "45") (name "/DAC1RNE2") (class "Default")
      (node (ref "J21") (pin "1") (pinfunction "1_1") (pintype "passive"))
      (node (ref "R55") (pin "1") (pinfunction "1_1") (pintype "passive"))
      (node (ref "U8") (pin "12") (pinfunction "+IN_12") (pintype "input"))
    )
    (net (code "46") (name "/DAC1RNER") (class "Default")
      (node (ref "R17") (pin "2") (pinfunction "2_2") (pintype "passive"))
      (node (ref "R21") (pin "1") (pinfunction "1_1") (pintype "passive"))
      (node (ref "R23") (pin "1") (pinfunction "1_1") (pintype "passive"))
      (node (ref "U9") (pin "2") (pinfunction "-IN_2") (pintype "input"))
    )
    (net (code "47") (name "/DAC1RNI") (class "Default")
      (node (ref "R16") (pin "1") (pinfunction "1_1") (pintype "passive"))
      (node (ref "R56") (pin "1") (pinfunction "1_1") (pintype "passive"))
    )
    (net (code "48") (name "/DAC1RNINT") (class "Default")
      (node (ref "R8") (pin "1") (pinfunction "1_1") (pintype "passive"))
      (node (ref "U1") (pin "82") (pinfunction "AN48/OA1N1/SEG24/RP20/PMRD/CN14/RD5_82") (pintype "passive"))
      (node (ref "U7") (pin "2") (pinfunction "-IN_2") (pintype "input"))
    )
    (net (code "49") (name "/DAC1RNIR") (class "Default")
      (node (ref "R16") (pin "2") (pinfunction "2_2") (pintype "passive"))
      (node (ref "R20") (pin "1") (pinfunction "1_1") (pintype "passive"))
      (node (ref "R22") (pin "1") (pinfunction "1_1") (pintype "passive"))
      (node (ref "R8") (pin "2") (pinfunction "2_2") (pintype "passive"))
    )
    (net (code "50") (name "/DAC1RNNEGE2") (class "Default")
      (node (ref "R38") (pin "2") (pinfunction "2_2") (pintype "passive"))
      (node (ref "R44") (pin "2") (pinfunction "2_2") (pintype "passive"))
      (node (ref "U8") (pin "13") (pinfunction "-IN_13") (pintype "input"))
    )
    (net (code "51") (name "/DAC1RNOUTE2") (class "Default")
      (node (ref "J19") (pin "1") (pinfunction "1_1") (pintype "passive"))
      (node (ref "R38") (pin "1") (pinfunction "1_1") (pintype "passive"))
      (node (ref "U8") (pin "14") (pinfunction "OUT_14") (pintype "output"))
    )
    (net (code "52") (name "/DAC1ROUT") (class "Default")
      (node (ref "J17") (pin "2") (pinfunction "2_2") (pintype "passive"))
      (node (ref "R18") (pin "2") (pinfunction "2_2") (pintype "passive"))
      (node (ref "U1") (pin "20") (pinfunction "PGEC3/AN5/OA1OUT/C1INA/SEG2/RP18/CN7/RB5_20") (pintype "passive"))
      (node (ref "U7") (pin "1") (pinfunction "OUT_1") (pintype "output"))
    )
    (net (code "53") (name "/DAC1ROUTE") (class "Default")
      (node (ref "J23") (pin "3") (pinfunction "3_3") (pintype "passive"))
      (node (ref "R19") (pin "2") (pinfunction "2_2") (pintype "passive"))
      (node (ref "U9") (pin "1") (pinfunction "OUT_1") (pintype "output"))
    )
    (net (code "54") (name "/DAC1RP") (class "Default")
      (node (ref "J22") (pin "3") (pinfunction "3_3") (pintype "passive"))
      (node (ref "R49") (pin "2") (pinfunction "2_2") (pintype "passive"))
      (node (ref "R50") (pin "2") (pinfunction "2_2") (pintype "passive"))
      (node (ref "R51") (pin "2") (pinfunction "2_2") (pintype "passive"))
      (node (ref "U2") (pin "10") (pinfunction "AN12/DAC1RP/RP12(1)/CN14/PMD0/RB12_10") (pintype "passive"))
    )
    (net (code "55") (name "/DAC1RPE") (class "Default")
      (node (ref "R15") (pin "1") (pinfunction "1_1") (pintype "passive"))
      (node (ref "R51") (pin "1") (pinfunction "1_1") (pintype "passive"))
    )
    (net (code "56") (name "/DAC1RPE2") (class "Default")
      (node (ref "J21") (pin "2") (pinfunction "2_2") (pintype "passive"))
      (node (ref "R49") (pin "1") (pinfunction "1_1") (pintype "passive"))
      (node (ref "U8") (pin "3") (pinfunction "+IN_3") (pintype "input"))
    )
    (net (code "57") (name "/DAC1RPER") (class "Default")
      (node (ref "R15") (pin "2") (pinfunction "2_2") (pintype "passive"))
      (node (ref "R19") (pin "1") (pinfunction "1_1") (pintype "passive"))
      (node (ref "U9") (pin "3") (pinfunction "+IN_3") (pintype "input"))
    )
    (net (code "58") (name "/DAC1RPI") (class "Default")
      (node (ref "R14") (pin "1") (pinfunction "1_1") (pintype "passive"))
      (node (ref "R50") (pin "1") (pinfunction "1_1") (pintype "passive"))
    )
    (net (code "59") (name "/DAC1RPINT") (class "Default")
      (node (ref "R6") (pin "1") (pinfunction "1_1") (pintype "passive"))
      (node (ref "U1") (pin "81") (pinfunction "AN47/OA1P4/SEG23/RP25/PMWR/CN13/RD4_81") (pintype "passive"))
      (node (ref "U7") (pin "3") (pinfunction "+IN_3") (pintype "input"))
    )
    (net (code "60") (name "/DAC1RPIR") (class "Default")
      (node (ref "R14") (pin "2") (pinfunction "2_2") (pintype "passive"))
      (node (ref "R18") (pin "1") (pinfunction "1_1") (pintype "passive"))
      (node (ref "R6") (pin "2") (pinfunction "2_2") (pintype "passive"))
    )
    (net (code "61") (name "/DAC1RPNEGE2") (class "Default")
      (node (ref "R37") (pin "2") (pinfunction "2_2") (pintype "passive"))
      (node (ref "R43") (pin "2") (pinfunction "2_2") (pintype "passive"))
      (node (ref "U8") (pin "2") (pinfunction "-IN_2") (pintype "input"))
    )
    (net (code "62") (name "/DAC1RPOUTE2") (class "Default")
      (node (ref "J19") (pin "3") (pinfunction "3_3") (pintype "passive"))
      (node (ref "R37") (pin "1") (pinfunction "1_1") (pintype "passive"))
      (node (ref "U8") (pin "1") (pinfunction "OUT_1") (pintype "output"))
    )
    (net (code "63") (name "/DACGND") (class "Default")
      (node (ref "C8") (pin "1") (pinfunction "1_1") (pintype "passive"))
      (node (ref "C9") (pin "1") (pinfunction "1_1") (pintype "passive"))
      (node (ref "R5") (pin "2") (pinfunction "2_2") (pintype "passive"))
      (node (ref "R73") (pin "2") (pinfunction "2_2") (pintype "passive"))
      (node (ref "U1") (pin "31") (pinfunction "AVSS_31") (pintype "passive"))
      (node (ref "U2") (pin "16") (pinfunction "AVSS_16") (pintype "passive"))
      (node (ref "U4") (pin "3") (pinfunction "Anode_3") (pintype "passive"))
      (node (ref "U7") (pin "4") (pinfunction "-VCC_4") (pintype "passive"))
    )
    (net (code "64") (name "/DACVDD") (class "Default")
      (node (ref "C9") (pin "2") (pinfunction "2_2") (pintype "passive"))
      (node (ref "R4") (pin "2") (pinfunction "2_2") (pintype "passive"))
      (node (ref "R76") (pin "1") (pinfunction "1_1") (pintype "passive"))
      (node (ref "U1") (pin "30") (pinfunction "AVDD_30") (pintype "passive"))
      (node (ref "U2") (pin "17") (pinfunction "AVDD_17") (pintype "passive"))
      (node (ref "U4") (pin "2") (pinfunction "Ref_2") (pintype "passive"))
      (node (ref "U7") (pin "8") (pinfunction "+VCC_8") (pintype "passive"))
    )
    (net (code "65") (name "/MCLRPIC24") (class "Default")
      (node (ref "C5") (pin "2") (pinfunction "2_2") (pintype "passive"))
      (node (ref "J3") (pin "1") (pinfunction "1_1") (pintype "passive"))
      (node (ref "R1") (pin "1") (pinfunction "1_1") (pintype "passive"))
      (node (ref "U1") (pin "13") (pinfunction "MCLR_13") (pintype "passive"))
    )
    (net (code "66") (name "/MCLRPIC33") (class "Default")
      (node (ref "C6") (pin "2") (pinfunction "2_2") (pintype "passive"))
      (node (ref "J4") (pin "1") (pinfunction "1_1") (pintype "passive"))
      (node (ref "R2") (pin "1") (pinfunction "1_1") (pintype "passive"))
      (node (ref "U2") (pin "18") (pinfunction "MCLR_18") (pintype "passive"))
    )
    (net (code "67") (name "/OSCI") (class "Default")
      (node (ref "C1") (pin "2") (pinfunction "2_2") (pintype "passive"))
      (node (ref "U1") (pin "63") (pinfunction "OSCI/CLKI/CN23/RC12_63") (pintype "passive"))
      (node (ref "Y1") (pin "1") (pinfunction "OSC_1") (pintype "passive"))
    )
    (net (code "68") (name "/OSCO") (class "Default")
      (node (ref "C2") (pin "2") (pinfunction "2_2") (pintype "passive"))
      (node (ref "U1") (pin "64") (pinfunction "OSCO/CLKO/CN22/RC15_64") (pintype "passive"))
      (node (ref "Y1") (pin "3") (pinfunction "OSC_3") (pintype "passive"))
    )
    (net (code "69") (name "/PGCPIC24") (class "Default")
      (node (ref "J3") (pin "5") (pinfunction "5_5") (pintype "passive"))
      (node (ref "U1") (pin "26") (pinfunction "PGEC2/AN6/OA1P3/RP6/LCDBIAS3/CN24/RB6_26") (pintype "passive"))
    )
    (net (code "70") (name "/PGCPIC33") (class "Default")
      (node (ref "J4") (pin "5") (pinfunction "5_5") (pintype "passive"))
      (node (ref "U2") (pin "9") (pinfunction "PGEC2/RP11(1)/CN15/PMD1/RB11_9") (pintype "passive"))
    )
    (net (code "71") (name "/PGDPIC24") (class "Default")
      (node (ref "J3") (pin "4") (pinfunction "4_4") (pintype "passive"))
      (node (ref "U1") (pin "27") (pinfunction "PGED2/AN7/COM6/SEG30/RP7/CN25/RB7_27") (pintype "passive"))
    )
    (net (code "72") (name "/PGDPIC33") (class "Default")
      (node (ref "J4") (pin "4") (pinfunction "4_4") (pintype "passive"))
      (node (ref "U2") (pin "8") (pinfunction "PGED2/EMCD2/RP10(1)/CN16/PMD2/RB10_8") (pintype "passive"))
    )
    (net (code "73") (name "/PMA0") (class "Default")
      (node (ref "U1") (pin "44") (pinfunction "AN15/SEG9/RP29/T2CK/REFO/CTED6/PMA0/CN12/RB15_44") (pintype "passive"))
    )
    (net (code "74") (name "/PMA1") (class "Default")
      (node (ref "U1") (pin "43") (pinfunction "AN14/OA2N4/SEG8/RP14/CTED5/CTPLS/PMA1/CN32/RB14_43") (pintype "passive"))
    )
    (net (code "75") (name "/PMA2") (class "Default")
      (node (ref "U1") (pin "14") (pinfunction "AN49/OA1P0/C2INC/SEG1/DAC1/RP27/PMA2/CN11/RG9_14") (pintype "passive"))
    )
    (net (code "76") (name "/PMA3") (class "Default")
      (node (ref "U1") (pin "12") (pinfunction "VLCAP2/AN19/OA1N2/C2IND/RP19/PMA3/CN10/RG8_12") (pintype "passive"))
    )
    (net (code "77") (name "/PMA4") (class "Default")
      (node (ref "U1") (pin "11") (pinfunction "VLCAP1/AN18/OA1N4/C1INC/RP26/PMA4/CN9/RG7_11") (pintype "passive"))
    )
    (net (code "78") (name "/PMA5") (class "Default")
      (node (ref "U1") (pin "10") (pinfunction "BGBUF2/AN17/OA1P1/C1IND/SEG0/RP21/T5CK/PMA5/CN8/RG6_10") (pintype "passive"))
    )
    (net (code "79") (name "/PMA6") (class "Default")
      (node (ref "U1") (pin "29") (pinfunction "CVREF+(1)/AVREF+(2)/SEG37/PMA6/CN42/RA10_29") (pintype "passive"))
    )
    (net (code "80") (name "/PMA7") (class "Default")
      (node (ref "U1") (pin "28") (pinfunction "CVREF-(1)/AVREF-(2)/SEG36/PMA7/CN41/RA9_28") (pintype "passive"))
    )
    (net (code "81") (name "/PMA8") (class "Default")
      (node (ref "U1") (pin "50") (pinfunction "CVREF/AN10/OA2P2/SEG11/RP17/SCL2(3)/PMA8/CN18/RF5_50") (pintype "passive"))
    )
    (net (code "82") (name "/PMA9") (class "Default")
      (node (ref "U1") (pin "49") (pinfunction "AN11/OA2N3/SEG10/RP10/SDA2(3)/T3CK/PMA9/CN17/RF4_49") (pintype "passive"))
    )
    (net (code "83") (name "/PMA10") (class "Default")
      (node (ref "U1") (pin "42") (pinfunction "AN13/OA2P3/SEG19/DAC2/CTED1/PMA10/CN31/RB13_42") (pintype "passive"))
    )
    (net (code "84") (name "/PMA11") (class "Default")
      (node (ref "U1") (pin "41") (pinfunction "AN12/COM5/SEG18/T1CK/CTED2/PMA11/CN30/RB12_41") (pintype "passive"))
    )
    (net (code "85") (name "/PMA12") (class "Default")
      (node (ref "U1") (pin "51") (pinfunction "AN30/SEG12/RP16/USBID/PMA12/CN71/RF3_51") (pintype "passive"))
    )
    (net (code "86") (name "/PMA13") (class "Default")
      (node (ref "U1") (pin "68") (pinfunction "AN40/SEG13/RP2/RTCC/DMLN/OCTRIG1/PMA13/CN53/RD8_68") (pintype "passive"))
    )
    (net (code "87") (name "/PMA14") (class "Default")
      (node (ref "U1") (pin "71") (pinfunction "AN42/OA2P0/C3INC/SEG16/RP12/PMA14/CS1/CN56/RD11_71") (pintype "passive"))
    )
    (net (code "88") (name "/PMA15") (class "Default")
      (node (ref "U1") (pin "70") (pinfunction "AN41/C3IND/SEG15/RP3/PMA15/CS2/CN55/RD10_70") (pintype "passive"))
    )
    (net (code "89") (name "/PMD0") (class "Default")
      (node (ref "U1") (pin "93") (pinfunction "COM3/PMD0/CN58/RE0_93") (pintype "passive"))
    )
    (net (code "90") (name "/PMD1") (class "Default")
      (node (ref "U1") (pin "94") (pinfunction "COM2/PMD1/CN59/RE1_94") (pintype "passive"))
    )
    (net (code "91") (name "/PMD2") (class "Default")
      (node (ref "U1") (pin "98") (pinfunction "COM1/PMD2/CN60/RE2_98") (pintype "passive"))
    )
    (net (code "92") (name "/PMD3") (class "Default")
      (node (ref "U1") (pin "99") (pinfunction "COM0/CTED9/PMD3/CN61/RE3_99") (pintype "passive"))
    )
    (net (code "93") (name "/PMD4") (class "Default")
      (node (ref "U1") (pin "100") (pinfunction "HLVDIN/SEG62/CTED8/PMD4/CN62/RE4_100") (pintype "passive"))
    )
    (net (code "94") (name "/PMD5") (class "Default")
      (node (ref "U1") (pin "3") (pinfunction "CTED4/PMD5/LCDBIAS2/CN63/RE5_3") (pintype "passive"))
    )
    (net (code "95") (name "/PMD6") (class "Default")
      (node (ref "U1") (pin "4") (pinfunction "PMD6/LCDBIAS1/CN64/RE6_4") (pintype "passive"))
    )
    (net (code "96") (name "/PMD7") (class "Default")
      (node (ref "U1") (pin "5") (pinfunction "PMD7/LCDBIAS0/CN65/RE7_5") (pintype "passive"))
    )
    (net (code "97") (name "/PMD8") (class "Default")
      (node (ref "U1") (pin "90") (pinfunction "SEG49/PMD8/CN77/RG0_90") (pintype "passive"))
    )
    (net (code "98") (name "/PMD9") (class "Default")
      (node (ref "U1") (pin "89") (pinfunction "SEG46/PMD9/CN78/RG1_89") (pintype "passive"))
    )
    (net (code "99") (name "/PMD10") (class "Default")
      (node (ref "U1") (pin "88") (pinfunction "COM4/SEG47/VCMPST2/PMD10/CN69/RF1_88") (pintype "passive"))
    )
    (net (code "100") (name "/PMD11") (class "Default")
      (node (ref "U1") (pin "87") (pinfunction "COM7/SEG27/VCMPST1/PMD11/CN68/RF0_87") (pintype "passive"))
    )
    (net (code "101") (name "/PMD12") (class "Default")
      (node (ref "U1") (pin "79") (pinfunction "AN45/SEG44/RPI42/PMD12/CN57/RD12_79") (pintype "passive"))
    )
    (net (code "102") (name "/PMD13") (class "Default")
      (node (ref "U1") (pin "80") (pinfunction "AN46/SEG45/PMD13/CN19/RD13_80") (pintype "passive"))
    )
    (net (code "103") (name "/PMD14") (class "Default")
      (node (ref "U1") (pin "83") (pinfunction "AN34/OA1P2/C3INB/SEG25/PMD14/CN15/RD6_83") (pintype "passive"))
    )
    (net (code "104") (name "/PMD15") (class "Default")
      (node (ref "U1") (pin "84") (pinfunction "AN20/C3INA/SEG26/PMD15/CN16/RD7_84") (pintype "passive"))
    )
    (net (code "105") (name "/RA0") (class "Default")
      (node (ref "U1") (pin "17") (pinfunction "TMS/SEG48/CTED0/CN33/RA0_17") (pintype "passive"))
    )
    (net (code "106") (name "/RA1") (class "Default")
      (node (ref "U1") (pin "38") (pinfunction "TCK/AN26/SEG31/CN34/RA1_38") (pintype "passive"))
    )
    (net (code "107") (name "/RA2") (class "Default")
      (node (ref "U1") (pin "58") (pinfunction "SEG55/SCL2/CN35/RA2_58") (pintype "passive"))
    )
    (net (code "108") (name "/RA3") (class "Default")
      (node (ref "U1") (pin "59") (pinfunction "SEG56/SDA2/PMA20/CN36/RA3_59") (pintype "passive"))
    )
    (net (code "109") (name "/RA4") (class "Default")
      (node (ref "U1") (pin "60") (pinfunction "TDI/AN36/SEG29/PMA21/CN37/RA4_60") (pintype "passive"))
    )
    (net (code "110") (name "/RA5") (class "Default")
      (node (ref "U1") (pin "61") (pinfunction "TDO/AN37/SEG28/CN38/RA5_61") (pintype "passive"))
    )
    (net (code "111") (name "/RA6") (class "Default")
      (node (ref "U1") (pin "91") (pinfunction "AN23/SEG57/CN39/RA6_91") (pintype "passive"))
    )
    (net (code "112") (name "/RA7") (class "Default")
      (node (ref "U1") (pin "92") (pinfunction "AN22/SEG58/PMA17/CN40/RA7_92") (pintype "passive"))
    )
    (net (code "113") (name "/RA14") (class "Default")
      (node (ref "U1") (pin "66") (pinfunction "AN38/SEG42/RPI36/SCL1/OCTRIG2/PMA22/CN43/RA14_66") (pintype "passive"))
    )
    (net (code "114") (name "/RA15") (class "Default")
      (node (ref "U1") (pin "67") (pinfunction "AN39/SEG43/RPI35/SDA1/PMBE1/CN44/RA15_67") (pintype "passive"))
    )
    (net (code "115") (name "/RB0") (class "Default")
      (node (ref "U1") (pin "25") (pinfunction "PGED1/CVREF+/AVREF+/DVREF+/BGBUF1/AN0/SEG7/RP0/CN2/RB0_25") (pintype "passive"))
    )
    (net (code "116") (name "/RB1") (class "Default")
      (node (ref "U1") (pin "24") (pinfunction "PGEC1/CVREF-/AVREF-/AN1/OA2P1/SEG6/RP1/CTED12/CN3/RB1_24") (pintype "passive"))
    )
    (net (code "117") (name "/RB2") (class "Default")
      (node (ref "U1") (pin "23") (pinfunction "AN2/OA2N2/CTCMP/C2INB/SEG5/RP13/T4CK/VMIO/CTED13/CN4/RB2_23") (pintype "passive"))
    )
    (net (code "118") (name "/RB5") (class "Default")
      (node (ref "U1") (pin "21") (pinfunction "PGED3/AN4/OA1N0/C1INB/SEG3/RP28/USBOEN/CN6/RB4_21") (pintype "passive"))
    )
    (net (code "119") (name "/RC1") (class "Default")
      (node (ref "U1") (pin "6") (pinfunction "AN8/OA1N1/SEG32/RPI38/CN45/RC1_6") (pintype "passive"))
    )
    (net (code "120") (name "/RC2") (class "Default")
      (node (ref "U1") (pin "7") (pinfunction "SEG51/RPI39/CN46/RC2_7") (pintype "passive"))
    )
    (net (code "121") (name "/RC3") (class "Default")
      (node (ref "U1") (pin "8") (pinfunction "AN9/SEG33/RPI40/CN47/RC3_8") (pintype "passive"))
    )
    (net (code "122") (name "/RC4") (class "Default")
      (node (ref "U1") (pin "9") (pinfunction "AN16/SEG52/RPI41/PMCS2/CN48/RC4_9") (pintype "passive"))
    )
    (net (code "123") (name "/RC13") (class "Default")
      (node (ref "U1") (pin "73") (pinfunction "SOSCI/RC13_73") (pintype "passive"))
    )
    (net (code "124") (name "/RC14") (class "Default")
      (node (ref "U1") (pin "74") (pinfunction "PWRLCLK/SOSCO/SCLKI/RPI37/RC14_74") (pintype "passive"))
    )
    (net (code "125") (name "/RD0") (class "Default")
      (node (ref "U1") (pin "72") (pinfunction "AN43/OA2N0/SEG17/RP11/VCMPST3/DMH/INT0/CN49/RD0_72") (pintype "passive"))
    )
    (net (code "126") (name "/RD1") (class "Default")
      (node (ref "U1") (pin "76") (pinfunction "AN35/SEG20/RP24/CN50/RD1(4)_76") (pintype "passive"))
    )
    (net (code "127") (name "/RD9") (class "Default")
      (node (ref "U1") (pin "69") (pinfunction "AN24/SEG14/RP4/DPLN/PMACK2/CN54/RD9_69") (pintype "passive"))
    )
    (net (code "128") (name "/RD14") (class "Default")
      (node (ref "U1") (pin "47") (pinfunction "AN28/SEG38/RPI43/CN20/RD14_47") (pintype "passive"))
    )
    (net (code "129") (name "/RD15") (class "Default")
      (node (ref "U1") (pin "48") (pinfunction "AN29/SEG39/RP5/CN21/RD15_48") (pintype "passive"))
    )
    (net (code "130") (name "/RE8") (class "Default")
      (node (ref "U1") (pin "18") (pinfunction "SEG34/RPI33/PMCS1/CN66/RE8_18") (pintype "passive"))
    )
    (net (code "131") (name "/RE9") (class "Default")
      (node (ref "U1") (pin "19") (pinfunction "AN21/SEG35/RPI34/PMA19/CN67/RE9_19") (pintype "passive"))
    )
    (net (code "132") (name "/RF2") (class "Default")
      (node (ref "U1") (pin "52") (pinfunction "AN31/SEG40/RP30/CN70/RF2_52") (pintype "passive"))
    )
    (net (code "133") (name "/RF8") (class "Default")
      (node (ref "U1") (pin "53") (pinfunction "AN32/SEG41/RP15/CN74/RF8_53") (pintype "passive"))
    )
    (net (code "134") (name "/RF12") (class "Default")
      (node (ref "U1") (pin "40") (pinfunction "SEG54/RPI32/CTED7/PMA18/CN75/RF12_40") (pintype "passive"))
    )
    (net (code "135") (name "/RF13") (class "Default")
      (node (ref "U1") (pin "39") (pinfunction "AN27/SEG53/RP31/CN76/RF13_39") (pintype "passive"))
    )
    (net (code "136") (name "/RG12") (class "Default")
      (node (ref "U1") (pin "96") (pinfunction "SEG60/CN79/RG12_96") (pintype "passive"))
    )
    (net (code "137") (name "/RG13") (class "Default")
      (node (ref "U1") (pin "97") (pinfunction "SEG61/CTED10/CN80/RG13_97") (pintype "passive"))
    )
    (net (code "138") (name "/RG14") (class "Default")
      (node (ref "U1") (pin "95") (pinfunction "SEG59/CTED11/PMA16/CN81/RG14_95") (pintype "passive"))
    )
    (net (code "139") (name "/RG15") (class "Default")
      (node (ref "U1") (pin "1") (pinfunction "AN33/SEG50/CTED3/CN82/RG15_1") (pintype "passive"))
    )
    (net (code "140") (name "/VBAT") (class "Default")
      (node (ref "U1") (pin "86") (pinfunction "VBAT_86") (pintype "passive"))
    )
    (net (code "141") (name "/VCAPPIC24") (class "Default")
      (node (ref "C3") (pin "2") (pinfunction "2_2") (pintype "passive"))
      (node (ref "U1") (pin "85") (pinfunction "VCAP_85") (pintype "passive"))
    )
    (net (code "142") (name "/VCAPPIC33") (class "Default")
      (node (ref "C4") (pin "2") (pinfunction "2_2") (pintype "passive"))
      (node (ref "U2") (pin "7") (pinfunction "VCAP_7") (pintype "passive"))
    )
    (net (code "143") (name "/VCC") (class "Default")
      (node (ref "C10") (pin "2") (pinfunction "2_2") (pintype "passive"))
      (node (ref "C11") (pin "2") (pinfunction "2_2") (pintype "passive"))
      (node (ref "C12") (pin "2") (pinfunction "2_2") (pintype "passive"))
      (node (ref "C13") (pin "2") (pinfunction "2_2") (pintype "passive"))
      (node (ref "C14") (pin "2") (pinfunction "2_2") (pintype "passive"))
      (node (ref "J17") (pin "1") (pinfunction "1_1") (pintype "passive"))
      (node (ref "R34") (pin "1") (pinfunction "1_1") (pintype "passive"))
      (node (ref "R42") (pin "1") (pinfunction "1_1") (pintype "passive"))
      (node (ref "U9") (pin "8") (pinfunction "+VCC_8") (pintype "passive"))
    )
    (net (code "144") (name "/VCC-") (class "Default")
      (node (ref "C10") (pin "1") (pinfunction "1_1") (pintype "passive"))
      (node (ref "C11") (pin "1") (pinfunction "1_1") (pintype "passive"))
      (node (ref "C12") (pin "1") (pinfunction "1_1") (pintype "passive"))
      (node (ref "C13") (pin "1") (pinfunction "1_1") (pintype "passive"))
      (node (ref "C14") (pin "1") (pinfunction "1_1") (pintype "passive"))
      (node (ref "J17") (pin "5") (pinfunction "5_5") (pintype "passive"))
      (node (ref "R35") (pin "1") (pinfunction "1_1") (pintype "passive"))
      (node (ref "R41") (pin "1") (pinfunction "1_1") (pintype "passive"))
      (node (ref "U9") (pin "4") (pinfunction "-VCC_4") (pintype "passive"))
    )
    (net (code "145") (name "/VCC1") (class "Default")
      (node (ref "U8") (pin "4") (pinfunction "+VCC_4") (pintype "passive"))
    )
    (net (code "146") (name "/VCC1-") (class "Default")
      (node (ref "R43") (pin "1") (pinfunction "1_1") (pintype "passive"))
      (node (ref "R44") (pin "1") (pinfunction "1_1") (pintype "passive"))
      (node (ref "R45") (pin "1") (pinfunction "1_1") (pintype "passive"))
      (node (ref "R46") (pin "1") (pinfunction "1_1") (pintype "passive"))
      (node (ref "U8") (pin "11") (pinfunction "GND_11") (pintype "passive"))
    )
    (net (code "147") (name "/VCC_HALF") (class "Default")
      (node (ref "J17") (pin "3") (pinfunction "3_3") (pintype "passive"))
      (node (ref "J23") (pin "2") (pinfunction "2_2") (pintype "passive"))
      (node (ref "R22") (pin "2") (pinfunction "2_2") (pintype "passive"))
      (node (ref "R32") (pin "2") (pinfunction "2_2") (pintype "passive"))
      (node (ref "R69") (pin "1") (pinfunction "1_1") (pintype "passive"))
      (node (ref "R70") (pin "1") (pinfunction "1_1") (pintype "passive"))
      (node (ref "R71") (pin "1") (pinfunction "1_1") (pintype "passive"))
      (node (ref "R72") (pin "1") (pinfunction "1_1") (pintype "passive"))
      (node (ref "R73") (pin "1") (pinfunction "1_1") (pintype "passive"))
      (node (ref "R74") (pin "1") (pinfunction "1_1") (pintype "passive"))
      (node (ref "R75") (pin "1") (pinfunction "1_1") (pintype "passive"))
    )
    (net (code "148") (name "/VCC_HALF_L") (class "Default")
      (node (ref "R33") (pin "2") (pinfunction "2_2") (pintype "passive"))
      (node (ref "R67") (pin "2") (pinfunction "2_2") (pintype "passive"))
      (node (ref "R69") (pin "2") (pinfunction "2_2") (pintype "passive"))
    )
    (net (code "149") (name "/VCC_HALF_L2") (class "Default")
      (node (ref "J20") (pin "2") (pinfunction "2_2") (pintype "passive"))
      (node (ref "R74") (pin "2") (pinfunction "2_2") (pintype "passive"))
    )
    (net (code "150") (name "/VCC_HALF_R") (class "Default")
      (node (ref "R23") (pin "2") (pinfunction "2_2") (pintype "passive"))
      (node (ref "R68") (pin "2") (pinfunction "2_2") (pintype "passive"))
      (node (ref "R70") (pin "2") (pinfunction "2_2") (pintype "passive"))
    )
    (net (code "151") (name "/VCC_HALF_R2") (class "Default")
      (node (ref "J19") (pin "2") (pinfunction "2_2") (pintype "passive"))
      (node (ref "R75") (pin "2") (pinfunction "2_2") (pintype "passive"))
    )
    (net (code "152") (name "/VDD") (class "Default")
      (node (ref "C7") (pin "2") (pinfunction "2_2") (pintype "passive"))
      (node (ref "J3") (pin "2") (pinfunction "2_2") (pintype "passive"))
      (node (ref "J4") (pin "2") (pinfunction "2_2") (pintype "passive"))
      (node (ref "R1") (pin "2") (pinfunction "2_2") (pintype "passive"))
      (node (ref "R2") (pin "2") (pinfunction "2_2") (pintype "passive"))
      (node (ref "R76") (pin "2") (pinfunction "2_2") (pintype "passive"))
      (node (ref "U1") (pin "16") (pinfunction "VDD_16") (pintype "passive"))
      (node (ref "U1") (pin "2") (pinfunction "VDD_2") (pintype "passive"))
      (node (ref "U1") (pin "46") (pinfunction "VDD_46") (pintype "passive"))
      (node (ref "U1") (pin "55") (pinfunction "VUSB3V3_55") (pintype "passive"))
      (node (ref "U1") (pin "62") (pinfunction "VDD_62") (pintype "passive"))
      (node (ref "U2") (pin "28") (pinfunction "VDD_28") (pintype "passive"))
      (node (ref "U2") (pin "40") (pinfunction "VDD_40") (pintype "passive"))
      (node (ref "U3") (pin "5") (pinfunction "Vout_5") (pintype "passive"))
    )
    (net (code "153") (name "/_PMA0") (class "Default")
      (node (ref "U2") (pin "19") (pinfunction "AN0/VREF+/CN2/RA0_19") (pintype "passive"))
    )
    (net (code "154") (name "/_PMA1") (class "Default")
      (node (ref "U2") (pin "20") (pinfunction "AN1/VREF-/CN3/RA1_20") (pintype "passive"))
    )
    (net (code "155") (name "/_PMA2") (class "Default")
      (node (ref "U2") (pin "30") (pinfunction "OSC1/CLKI/CN30/RA2_30") (pintype "passive"))
    )
    (net (code "156") (name "/_PMA3") (class "Default")
      (node (ref "U2") (pin "31") (pinfunction "OSC2/CLKO/CN29/RA3_31") (pintype "passive"))
    )
    (net (code "157") (name "/_PMA4") (class "Default")
      (node (ref "U2") (pin "34") (pinfunction "SOSCO/T1CK/CN0/RA4_34") (pintype "passive"))
    )
    (net (code "158") (name "/_PMA5") (class "Default")
      (node (ref "U2") (pin "4") (pinfunction "RP24(1)/CN20/PMA5/RC8_4") (pintype "passive"))
    )
    (net (code "159") (name "/_PMA6") (class "Default")
      (node (ref "U2") (pin "5") (pinfunction "RP25(1)/CN19/PMA6/RC9_5") (pintype "passive"))
    )
    (net (code "160") (name "/_PMA7") (class "Default")
      (node (ref "U2") (pin "13") (pinfunction "TCK/PMA7/RA7_13") (pintype "passive"))
    )
    (net (code "161") (name "/_PMA8") (class "Default")
      (node (ref "U2") (pin "32") (pinfunction "TDO/PMA8/RA8_32") (pintype "passive"))
    )
    (net (code "162") (name "/_PMA9") (class "Default")
      (node (ref "U2") (pin "35") (pinfunction "TDI/PMA9/RA9_35") (pintype "passive"))
    )
    (net (code "163") (name "/_PMA10") (class "Default")
      (node (ref "U2") (pin "12") (pinfunction "TMS/PMA10/RA10_12") (pintype "passive"))
    )
    (net (code "164") (name "/_PMD0") (class "Default")
      (node (ref "U2") (pin "21") (pinfunction "PGED1/AN2/C2IN-/RP0(1)/CN4/RB0_21") (pintype "passive"))
    )
    (net (code "165") (name "/_PMD1") (class "Default")
      (node (ref "U2") (pin "22") (pinfunction "PGEC1/AN3/C2IN+/RP1(1)/CN5/RB1_22") (pintype "passive"))
    )
    (net (code "166") (name "/_PMD2") (class "Default")
      (node (ref "U2") (pin "23") (pinfunction "AN4/C1IN-/RP2(1)/CN6/RB2_23") (pintype "passive"))
    )
    (net (code "167") (name "/_PMD3") (class "Default")
      (node (ref "U2") (pin "24") (pinfunction "AN5/C1IN+/RP3(1)/CN7/RB3_24") (pintype "passive"))
    )
    (net (code "168") (name "/_PMD4") (class "Default")
      (node (ref "U2") (pin "33") (pinfunction "SOSCI/RP4(1)/CN1/RB4_33") (pintype "passive"))
    )
    (net (code "169") (name "/_PMD5") (class "Default")
      (node (ref "U2") (pin "41") (pinfunction "PGED3/ASDA1/RP5(1)/CN27/PMD7/RB5_41") (pintype "passive"))
    )
    (net (code "170") (name "/_PMD6") (class "Default")
      (node (ref "U2") (pin "42") (pinfunction "PGEC3/ASCL1/RP6(1)/CN24/PMD6/RB6_42") (pintype "passive"))
    )
    (net (code "171") (name "/_PMD7") (class "Default")
      (node (ref "U2") (pin "43") (pinfunction "INT0/RP7(1)/CN23/PMD5/RB7_43") (pintype "passive"))
    )
    (net (code "172") (name "/_PMD8") (class "Default")
      (node (ref "U2") (pin "44") (pinfunction "SCL1/RP8(1)/CN22/PMD4/RB8_44") (pintype "passive"))
    )
    (net (code "173") (name "/_PMD9") (class "Default")
      (node (ref "U2") (pin "1") (pinfunction "SDA1/RP9(1)/CN21/PMD3/RB9_1") (pintype "passive"))
    )
    (net (code "174") (name "/_PMD10") (class "Default")
      (node (ref "U2") (pin "27") (pinfunction "AN8/CVREF/RP18(1)/PMA2/CN10/RC2_27") (pintype "passive"))
    )
    (net (code "175") (name "/_PMD11") (class "Default")
      (node (ref "U2") (pin "36") (pinfunction "RP19(1)/CN28/PMBE/RC3_36") (pintype "passive"))
    )
    (net (code "176") (name "/_PMD12") (class "Default")
      (node (ref "U2") (pin "37") (pinfunction "RP20(1)/CN25/PMA4/RC4_37") (pintype "passive"))
    )
    (net (code "177") (name "/_PMD13") (class "Default")
      (node (ref "U2") (pin "38") (pinfunction "RP21(1)/CN26/PMA3/RC5_38") (pintype "passive"))
    )
    (net (code "178") (name "/_PMD14") (class "Default")
      (node (ref "U2") (pin "2") (pinfunction "RP22(1)/CN18/PMA1/RC6_2") (pintype "passive"))
    )
    (net (code "179") (name "/_PMD15") (class "Default")
      (node (ref "U2") (pin "3") (pinfunction "RP23(1)/CN17/PMA0/RC7_3") (pintype "passive"))
    )
    (net (code "180") (name "GND") (class "Default")
      (node (ref "C1") (pin "1") (pinfunction "1_1") (pintype "passive"))
      (node (ref "C2") (pin "1") (pinfunction "1_1") (pintype "passive"))
      (node (ref "C3") (pin "1") (pinfunction "1_1") (pintype "passive"))
      (node (ref "C4") (pin "1") (pinfunction "1_1") (pintype "passive"))
      (node (ref "C5") (pin "1") (pinfunction "1_1") (pintype "passive"))
      (node (ref "C6") (pin "1") (pinfunction "1_1") (pintype "passive"))
      (node (ref "C7") (pin "1") (pinfunction "1_1") (pintype "passive"))
      (node (ref "D1") (pin "2") (pinfunction "AAAA_2") (pintype "passive"))
      (node (ref "D1") (pin "5") (pinfunction "C4_5") (pintype "passive"))
      (node (ref "D2") (pin "1") (pinfunction "A_1") (pintype "passive"))
      (node (ref "D3") (pin "1") (pinfunction "A_1") (pintype "passive"))
      (node (ref "J14") (pin "2") (pinfunction "2_2") (pintype "passive"))
      (node (ref "J3") (pin "3") (pinfunction "3_3") (pintype "passive"))
      (node (ref "J4") (pin "3") (pinfunction "3_3") (pintype "passive"))
      (node (ref "J5") (pin "5") (pinfunction "5_5") (pintype "passive"))
      (node (ref "J5") (pin "6") (pinfunction "6_6") (pintype "passive"))
      (node (ref "J5") (pin "7") (pinfunction "7_7") (pintype "passive"))
      (node (ref "J5") (pin "8") (pinfunction "8_8") (pintype "passive"))
      (node (ref "J5") (pin "9") (pinfunction "9_9") (pintype "passive"))
      (node (ref "R41") (pin "2") (pinfunction "2_2") (pintype "passive"))
      (node (ref "R5") (pin "1") (pinfunction "1_1") (pintype "passive"))
      (node (ref "R71") (pin "2") (pinfunction "2_2") (pintype "passive"))
      (node (ref "U1") (pin "15") (pinfunction "VSS_15") (pintype "passive"))
      (node (ref "U1") (pin "45") (pinfunction "VSS_45") (pintype "passive"))
      (node (ref "U1") (pin "65") (pinfunction "VSS_65") (pintype "passive"))
      (node (ref "U1") (pin "75") (pinfunction "VSS_75") (pintype "passive"))
      (node (ref "U2") (pin "29") (pinfunction "VSS_29") (pintype "passive"))
      (node (ref "U2") (pin "39") (pinfunction "VSS_39") (pintype "passive"))
      (node (ref "U2") (pin "6") (pinfunction "VSS_6") (pintype "passive"))
      (node (ref "U3") (pin "2") (pinfunction "GND_2") (pintype "passive"))
    )
    (net (code "181") (name "unconnected-(J6-Pad1)") (class "Default")
      (node (ref "J6") (pin "1") (pinfunction "1_1") (pintype "passive"))
    )
    (net (code "182") (name "unconnected-(J7-Pad1)") (class "Default")
      (node (ref "J7") (pin "1") (pinfunction "1_1") (pintype "passive"))
    )
    (net (code "183") (name "unconnected-(J8-Pad1)") (class "Default")
      (node (ref "J8") (pin "1") (pinfunction "1_1") (pintype "passive"))
    )
    (net (code "184") (name "unconnected-(J9-Pad1)") (class "Default")
      (node (ref "J9") (pin "1") (pinfunction "1_1") (pintype "passive"))
    )
    (net (code "185") (name "unconnected-(U3-NC-Pad4)") (class "Default")
      (node (ref "U3") (pin "4") (pinfunction "NC_4") (pintype "passive"))
    )
    (net (code "186") (name "unconnected-(Y1-NC-Pad2)") (class "Default")
      (node (ref "Y1") (pin "2") (pinfunction "NC_2") (pintype "passive"))
    )
    (net (code "187") (name "unconnected-(Y1-NC-Pad4)") (class "Default")
      (node (ref "Y1") (pin "4") (pinfunction "NC_4") (pintype "passive"))
    )
  )
)
